# 8_-_Z7010_B34_AR238_MIPI.net
KiCad netlist of a schematic drawn in Altium Designer
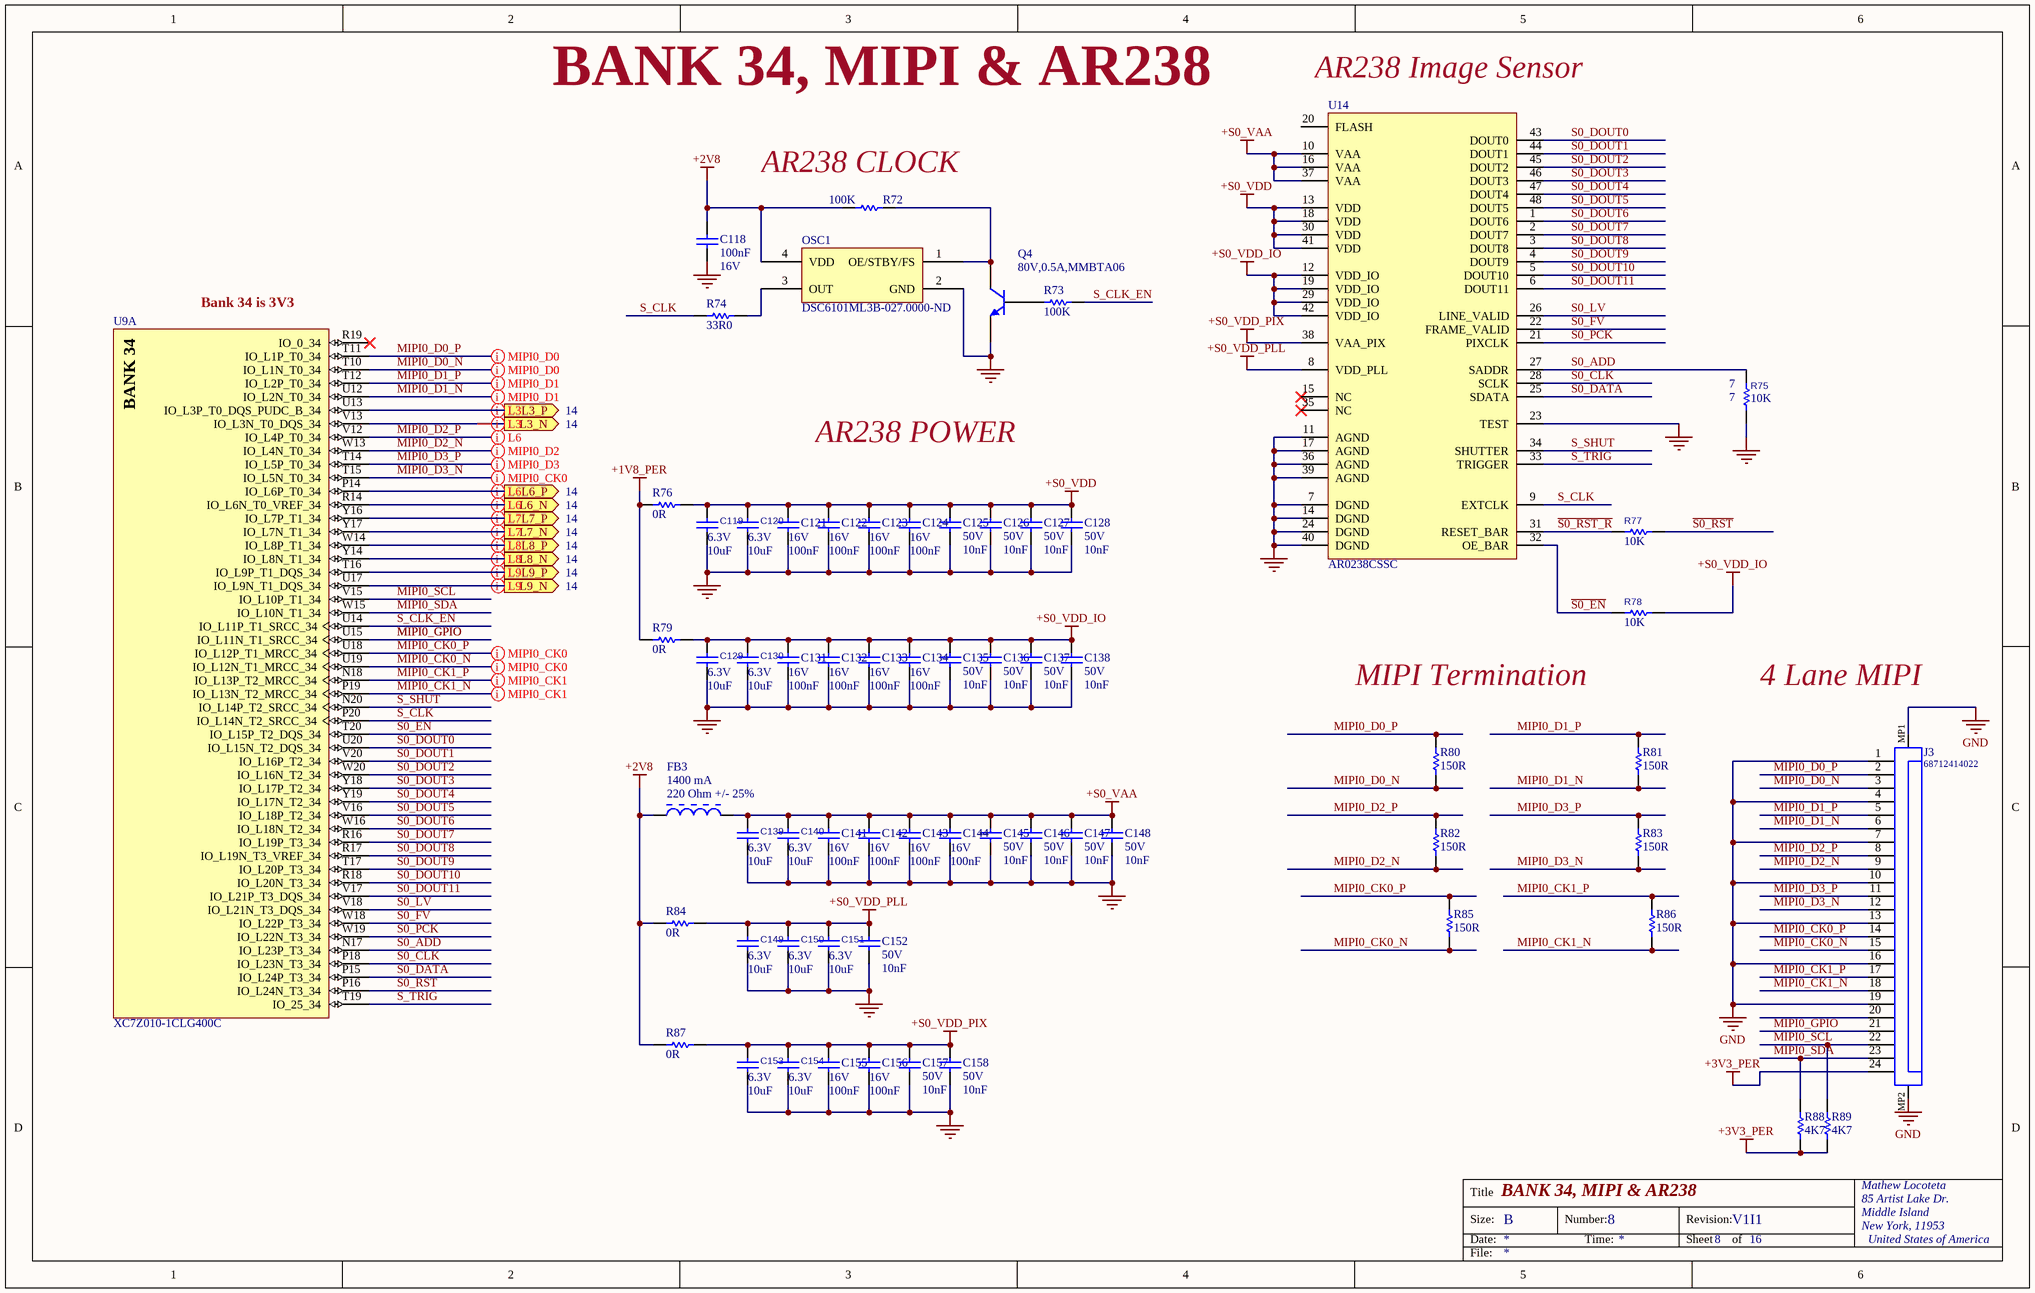
[diagram p0: [8] - Z7010 B34, AR238, MIPI.SchDoc]

(export (version "E")
  (design (tool "Eeschema 10.0.6"))
  (components
    (comp (ref "C118")
      (value "0.1uF,16V")
      (footprint "C0402")
      (description "CAP CER 0.1UF 16V X7R 0402")
      (fields
        (field (name "MANUFACTURER") "Samsung")
        (field (name "MANUFACTURER PART NUMBER") "CL05B104KO5VPNC")
        (field (name "CAPACITANCE") "100nF")
        (field (name "VOLTAGE RATING") "16V")
      )
      (libsource (lib "DVXC4+ ECU (2)") (part "CL05B104KO5VPNC"))
    )
    (comp (ref "C119")
      (value "10uF,6V3")
      (footprint "C0603")
      (description "CAP CER 10UF 6.3V X5R 0603")
      (fields
        (field (name "MANUFACTURER") "Taiyo Yuden")
        (field (name "MANUFACTURER PART NUMBER") "JMK107ABJ106MAHT")
        (field (name "CAPACITANCE") "10uF")
        (field (name "VOLTAGE RATING") "6.3V")
      )
      (libsource (lib "DVXC4+ ECU (2)") (part "JMK107ABJ106MAHT"))
    )
    (comp (ref "C120")
      (value "10uF,6V3")
      (footprint "C0603")
      (description "CAP CER 10UF 6.3V X5R 0603")
      (fields
        (field (name "MANUFACTURER") "Taiyo Yuden")
        (field (name "MANUFACTURER PART NUMBER") "JMK107ABJ106MAHT")
        (field (name "CAPACITANCE") "10uF")
        (field (name "VOLTAGE RATING") "6.3V")
      )
      (libsource (lib "DVXC4+ ECU (2)") (part "JMK107ABJ106MAHT"))
    )
    (comp (ref "C121")
      (value "0.1uF,16V")
      (footprint "C0402")
      (description "CAP CER 0.1UF 16V X7R 0402")
      (fields
        (field (name "MANUFACTURER") "Samsung")
        (field (name "MANUFACTURER PART NUMBER") "CL05B104KO5VPNC")
        (field (name "CAPACITANCE") "100nF")
        (field (name "VOLTAGE RATING") "16V")
      )
      (libsource (lib "DVXC4+ ECU (2)") (part "CL05B104KO5VPNC"))
    )
    (comp (ref "C122")
      (value "0.1uF,16V")
      (footprint "C0402")
      (description "CAP CER 0.1UF 16V X7R 0402")
      (fields
        (field (name "MANUFACTURER") "Samsung")
        (field (name "MANUFACTURER PART NUMBER") "CL05B104KO5VPNC")
        (field (name "CAPACITANCE") "100nF")
        (field (name "VOLTAGE RATING") "16V")
      )
      (libsource (lib "DVXC4+ ECU (2)") (part "CL05B104KO5VPNC"))
    )
    (comp (ref "C123")
      (value "0.1uF,16V")
      (footprint "C0402")
      (description "CAP CER 0.1UF 16V X7R 0402")
      (fields
        (field (name "MANUFACTURER") "Samsung")
        (field (name "MANUFACTURER PART NUMBER") "CL05B104KO5VPNC")
        (field (name "CAPACITANCE") "100nF")
        (field (name "VOLTAGE RATING") "16V")
      )
      (libsource (lib "DVXC4+ ECU (2)") (part "CL05B104KO5VPNC"))
    )
    (comp (ref "C124")
      (value "0.1uF,16V")
      (footprint "C0402")
      (description "CAP CER 0.1UF 16V X7R 0402")
      (fields
        (field (name "MANUFACTURER") "Samsung")
        (field (name "MANUFACTURER PART NUMBER") "CL05B104KO5VPNC")
        (field (name "CAPACITANCE") "100nF")
        (field (name "VOLTAGE RATING") "16V")
      )
      (libsource (lib "DVXC4+ ECU (2)") (part "CL05B104KO5VPNC"))
    )
    (comp (ref "C125")
      (value "CC0402KRX7R9BB103")
      (footprint "CAPC1005X55X25ML5T10")
      (description "Chip Capacitor, 10 nF, +/- 10%, 50 V, -55 to 125 degC, 0402 (1005 Metric), RoHS, Tape and Reel")
      (fields
        (field (name "MANUFACTURER") "Yageo")
        (field (name "VOLTAGE RATING (DC)") "50V")
        (field (name "TOLERANCE") "10%")
        (field (name "CAPACITANCE") "10nF")
      )
      (libsource (lib "Altium Content Vault") (part "CAP-NP-2"))
    )
    (comp (ref "C126")
      (value "CC0402KRX7R9BB103")
      (footprint "CAPC1005X55X25ML5T10")
      (description "Chip Capacitor, 10 nF, +/- 10%, 50 V, -55 to 125 degC, 0402 (1005 Metric), RoHS, Tape and Reel")
      (fields
        (field (name "MANUFACTURER") "Yageo")
        (field (name "VOLTAGE RATING (DC)") "50V")
        (field (name "TOLERANCE") "10%")
        (field (name "CAPACITANCE") "10nF")
      )
      (libsource (lib "Altium Content Vault") (part "CAP-NP-2"))
    )
    (comp (ref "C127")
      (value "CC0402KRX7R9BB103")
      (footprint "CAPC1005X55X25ML5T10")
      (description "Chip Capacitor, 10 nF, +/- 10%, 50 V, -55 to 125 degC, 0402 (1005 Metric), RoHS, Tape and Reel")
      (fields
        (field (name "MANUFACTURER") "Yageo")
        (field (name "VOLTAGE RATING (DC)") "50V")
        (field (name "TOLERANCE") "10%")
        (field (name "CAPACITANCE") "10nF")
      )
      (libsource (lib "Altium Content Vault") (part "CAP-NP-2"))
    )
    (comp (ref "C128")
      (value "CC0402KRX7R9BB103")
      (footprint "CAPC1005X55X25ML5T10")
      (description "Chip Capacitor, 10 nF, +/- 10%, 50 V, -55 to 125 degC, 0402 (1005 Metric), RoHS, Tape and Reel")
      (fields
        (field (name "MANUFACTURER") "Yageo")
        (field (name "VOLTAGE RATING (DC)") "50V")
        (field (name "TOLERANCE") "10%")
        (field (name "CAPACITANCE") "10nF")
      )
      (libsource (lib "Altium Content Vault") (part "CAP-NP-2"))
    )
    (comp (ref "C129")
      (value "10uF,6V3")
      (footprint "C0603")
      (description "CAP CER 10UF 6.3V X5R 0603")
      (fields
        (field (name "MANUFACTURER") "Taiyo Yuden")
        (field (name "MANUFACTURER PART NUMBER") "JMK107ABJ106MAHT")
        (field (name "CAPACITANCE") "10uF")
        (field (name "VOLTAGE RATING") "6.3V")
      )
      (libsource (lib "DVXC4+ ECU (2)") (part "JMK107ABJ106MAHT"))
    )
    (comp (ref "C130")
      (value "10uF,6V3")
      (footprint "C0603")
      (description "CAP CER 10UF 6.3V X5R 0603")
      (fields
        (field (name "MANUFACTURER") "Taiyo Yuden")
        (field (name "MANUFACTURER PART NUMBER") "JMK107ABJ106MAHT")
        (field (name "CAPACITANCE") "10uF")
        (field (name "VOLTAGE RATING") "6.3V")
      )
      (libsource (lib "DVXC4+ ECU (2)") (part "JMK107ABJ106MAHT"))
    )
    (comp (ref "C131")
      (value "0.1uF,16V")
      (footprint "C0402")
      (description "CAP CER 0.1UF 16V X7R 0402")
      (fields
        (field (name "MANUFACTURER") "Samsung")
        (field (name "MANUFACTURER PART NUMBER") "CL05B104KO5VPNC")
        (field (name "CAPACITANCE") "100nF")
        (field (name "VOLTAGE RATING") "16V")
      )
      (libsource (lib "DVXC4+ ECU (2)") (part "CL05B104KO5VPNC"))
    )
    (comp (ref "C132")
      (value "0.1uF,16V")
      (footprint "C0402")
      (description "CAP CER 0.1UF 16V X7R 0402")
      (fields
        (field (name "MANUFACTURER") "Samsung")
        (field (name "MANUFACTURER PART NUMBER") "CL05B104KO5VPNC")
        (field (name "CAPACITANCE") "100nF")
        (field (name "VOLTAGE RATING") "16V")
      )
      (libsource (lib "DVXC4+ ECU (2)") (part "CL05B104KO5VPNC"))
    )
    (comp (ref "C133")
      (value "0.1uF,16V")
      (footprint "C0402")
      (description "CAP CER 0.1UF 16V X7R 0402")
      (fields
        (field (name "MANUFACTURER") "Samsung")
        (field (name "MANUFACTURER PART NUMBER") "CL05B104KO5VPNC")
        (field (name "CAPACITANCE") "100nF")
        (field (name "VOLTAGE RATING") "16V")
      )
      (libsource (lib "DVXC4+ ECU (2)") (part "CL05B104KO5VPNC"))
    )
    (comp (ref "C134")
      (value "0.1uF,16V")
      (footprint "C0402")
      (description "CAP CER 0.1UF 16V X7R 0402")
      (fields
        (field (name "MANUFACTURER") "Samsung")
        (field (name "MANUFACTURER PART NUMBER") "CL05B104KO5VPNC")
        (field (name "CAPACITANCE") "100nF")
        (field (name "VOLTAGE RATING") "16V")
      )
      (libsource (lib "DVXC4+ ECU (2)") (part "CL05B104KO5VPNC"))
    )
    (comp (ref "C135")
      (value "CC0402KRX7R9BB103")
      (footprint "CAPC1005X55X25ML5T10")
      (description "Chip Capacitor, 10 nF, +/- 10%, 50 V, -55 to 125 degC, 0402 (1005 Metric), RoHS, Tape and Reel")
      (fields
        (field (name "MANUFACTURER") "Yageo")
        (field (name "VOLTAGE RATING (DC)") "50V")
        (field (name "TOLERANCE") "10%")
        (field (name "CAPACITANCE") "10nF")
      )
      (libsource (lib "Altium Content Vault") (part "CAP-NP-2"))
    )
    (comp (ref "C136")
      (value "CC0402KRX7R9BB103")
      (footprint "CAPC1005X55X25ML5T10")
      (description "Chip Capacitor, 10 nF, +/- 10%, 50 V, -55 to 125 degC, 0402 (1005 Metric), RoHS, Tape and Reel")
      (fields
        (field (name "MANUFACTURER") "Yageo")
        (field (name "VOLTAGE RATING (DC)") "50V")
        (field (name "TOLERANCE") "10%")
        (field (name "CAPACITANCE") "10nF")
      )
      (libsource (lib "Altium Content Vault") (part "CAP-NP-2"))
    )
    (comp (ref "C137")
      (value "CC0402KRX7R9BB103")
      (footprint "CAPC1005X55X25ML5T10")
      (description "Chip Capacitor, 10 nF, +/- 10%, 50 V, -55 to 125 degC, 0402 (1005 Metric), RoHS, Tape and Reel")
      (fields
        (field (name "MANUFACTURER") "Yageo")
        (field (name "VOLTAGE RATING (DC)") "50V")
        (field (name "TOLERANCE") "10%")
        (field (name "CAPACITANCE") "10nF")
      )
      (libsource (lib "Altium Content Vault") (part "CAP-NP-2"))
    )
    (comp (ref "C138")
      (value "CC0402KRX7R9BB103")
      (footprint "CAPC1005X55X25ML5T10")
      (description "Chip Capacitor, 10 nF, +/- 10%, 50 V, -55 to 125 degC, 0402 (1005 Metric), RoHS, Tape and Reel")
      (fields
        (field (name "MANUFACTURER") "Yageo")
        (field (name "VOLTAGE RATING (DC)") "50V")
        (field (name "TOLERANCE") "10%")
        (field (name "CAPACITANCE") "10nF")
      )
      (libsource (lib "Altium Content Vault") (part "CAP-NP-2"))
    )
    (comp (ref "C139")
      (value "10uF,6V3")
      (footprint "C0603")
      (description "CAP CER 10UF 6.3V X5R 0603")
      (fields
        (field (name "MANUFACTURER") "Taiyo Yuden")
        (field (name "MANUFACTURER PART NUMBER") "JMK107ABJ106MAHT")
        (field (name "CAPACITANCE") "10uF")
        (field (name "VOLTAGE RATING") "6.3V")
      )
      (libsource (lib "DVXC4+ ECU (2)") (part "JMK107ABJ106MAHT"))
    )
    (comp (ref "C140")
      (value "10uF,6V3")
      (footprint "C0603")
      (description "CAP CER 10UF 6.3V X5R 0603")
      (fields
        (field (name "MANUFACTURER") "Taiyo Yuden")
        (field (name "MANUFACTURER PART NUMBER") "JMK107ABJ106MAHT")
        (field (name "CAPACITANCE") "10uF")
        (field (name "VOLTAGE RATING") "6.3V")
      )
      (libsource (lib "DVXC4+ ECU (2)") (part "JMK107ABJ106MAHT"))
    )
    (comp (ref "C141")
      (value "0.1uF,16V")
      (footprint "C0402")
      (description "CAP CER 0.1UF 16V X7R 0402")
      (fields
        (field (name "MANUFACTURER") "Samsung")
        (field (name "MANUFACTURER PART NUMBER") "CL05B104KO5VPNC")
        (field (name "CAPACITANCE") "100nF")
        (field (name "VOLTAGE RATING") "16V")
      )
      (libsource (lib "DVXC4+ ECU (2)") (part "CL05B104KO5VPNC"))
    )
    (comp (ref "C142")
      (value "0.1uF,16V")
      (footprint "C0402")
      (description "CAP CER 0.1UF 16V X7R 0402")
      (fields
        (field (name "MANUFACTURER") "Samsung")
        (field (name "MANUFACTURER PART NUMBER") "CL05B104KO5VPNC")
        (field (name "CAPACITANCE") "100nF")
        (field (name "VOLTAGE RATING") "16V")
      )
      (libsource (lib "DVXC4+ ECU (2)") (part "CL05B104KO5VPNC"))
    )
    (comp (ref "C143")
      (value "0.1uF,16V")
      (footprint "C0402")
      (description "CAP CER 0.1UF 16V X7R 0402")
      (fields
        (field (name "MANUFACTURER") "Samsung")
        (field (name "MANUFACTURER PART NUMBER") "CL05B104KO5VPNC")
        (field (name "CAPACITANCE") "100nF")
        (field (name "VOLTAGE RATING") "16V")
      )
      (libsource (lib "DVXC4+ ECU (2)") (part "CL05B104KO5VPNC"))
    )
    (comp (ref "C144")
      (value "0.1uF,16V")
      (footprint "C0402")
      (description "CAP CER 0.1UF 16V X7R 0402")
      (fields
        (field (name "MANUFACTURER") "Samsung")
        (field (name "MANUFACTURER PART NUMBER") "CL05B104KO5VPNC")
        (field (name "CAPACITANCE") "100nF")
        (field (name "VOLTAGE RATING") "16V")
      )
      (libsource (lib "DVXC4+ ECU (2)") (part "CL05B104KO5VPNC"))
    )
    (comp (ref "C145")
      (value "CC0402KRX7R9BB103")
      (footprint "CAPC1005X55X25ML5T10")
      (description "Chip Capacitor, 10 nF, +/- 10%, 50 V, -55 to 125 degC, 0402 (1005 Metric), RoHS, Tape and Reel")
      (fields
        (field (name "MANUFACTURER") "Yageo")
        (field (name "VOLTAGE RATING (DC)") "50V")
        (field (name "TOLERANCE") "10%")
        (field (name "CAPACITANCE") "10nF")
      )
      (libsource (lib "Altium Content Vault") (part "CAP-NP-2"))
    )
    (comp (ref "C146")
      (value "CC0402KRX7R9BB103")
      (footprint "CAPC1005X55X25ML5T10")
      (description "Chip Capacitor, 10 nF, +/- 10%, 50 V, -55 to 125 degC, 0402 (1005 Metric), RoHS, Tape and Reel")
      (fields
        (field (name "MANUFACTURER") "Yageo")
        (field (name "VOLTAGE RATING (DC)") "50V")
        (field (name "TOLERANCE") "10%")
        (field (name "CAPACITANCE") "10nF")
      )
      (libsource (lib "Altium Content Vault") (part "CAP-NP-2"))
    )
    (comp (ref "C147")
      (value "CC0402KRX7R9BB103")
      (footprint "CAPC1005X55X25ML5T10")
      (description "Chip Capacitor, 10 nF, +/- 10%, 50 V, -55 to 125 degC, 0402 (1005 Metric), RoHS, Tape and Reel")
      (fields
        (field (name "MANUFACTURER") "Yageo")
        (field (name "VOLTAGE RATING (DC)") "50V")
        (field (name "TOLERANCE") "10%")
        (field (name "CAPACITANCE") "10nF")
      )
      (libsource (lib "Altium Content Vault") (part "CAP-NP-2"))
    )
    (comp (ref "C148")
      (value "CC0402KRX7R9BB103")
      (footprint "CAPC1005X55X25ML5T10")
      (description "Chip Capacitor, 10 nF, +/- 10%, 50 V, -55 to 125 degC, 0402 (1005 Metric), RoHS, Tape and Reel")
      (fields
        (field (name "MANUFACTURER") "Yageo")
        (field (name "VOLTAGE RATING (DC)") "50V")
        (field (name "TOLERANCE") "10%")
        (field (name "CAPACITANCE") "10nF")
      )
      (libsource (lib "Altium Content Vault") (part "CAP-NP-2"))
    )
    (comp (ref "C149")
      (value "10uF,6V3")
      (footprint "C0603")
      (description "CAP CER 10UF 6.3V X5R 0603")
      (fields
        (field (name "MANUFACTURER") "Taiyo Yuden")
        (field (name "MANUFACTURER PART NUMBER") "JMK107ABJ106MAHT")
        (field (name "CAPACITANCE") "10uF")
        (field (name "VOLTAGE RATING") "6.3V")
      )
      (libsource (lib "DVXC4+ ECU (2)") (part "JMK107ABJ106MAHT"))
    )
    (comp (ref "C150")
      (value "10uF,6V3")
      (footprint "C0603")
      (description "CAP CER 10UF 6.3V X5R 0603")
      (fields
        (field (name "MANUFACTURER") "Taiyo Yuden")
        (field (name "MANUFACTURER PART NUMBER") "JMK107ABJ106MAHT")
        (field (name "CAPACITANCE") "10uF")
        (field (name "VOLTAGE RATING") "6.3V")
      )
      (libsource (lib "DVXC4+ ECU (2)") (part "JMK107ABJ106MAHT"))
    )
    (comp (ref "C151")
      (value "10uF,6V3")
      (footprint "C0603")
      (description "CAP CER 10UF 6.3V X5R 0603")
      (fields
        (field (name "MANUFACTURER") "Taiyo Yuden")
        (field (name "MANUFACTURER PART NUMBER") "JMK107ABJ106MAHT")
        (field (name "CAPACITANCE") "10uF")
        (field (name "VOLTAGE RATING") "6.3V")
      )
      (libsource (lib "DVXC4+ ECU (2)") (part "JMK107ABJ106MAHT"))
    )
    (comp (ref "C152")
      (value "CC0402KRX7R9BB103")
      (footprint "CAPC1005X55X25ML5T10")
      (description "Chip Capacitor, 10 nF, +/- 10%, 50 V, -55 to 125 degC, 0402 (1005 Metric), RoHS, Tape and Reel")
      (fields
        (field (name "MANUFACTURER") "Yageo")
        (field (name "VOLTAGE RATING (DC)") "50V")
        (field (name "TOLERANCE") "10%")
        (field (name "CAPACITANCE") "10nF")
      )
      (libsource (lib "Altium Content Vault") (part "CAP-NP-2"))
    )
    (comp (ref "C153")
      (value "10uF,6V3")
      (footprint "C0603")
      (description "CAP CER 10UF 6.3V X5R 0603")
      (fields
        (field (name "MANUFACTURER") "Taiyo Yuden")
        (field (name "MANUFACTURER PART NUMBER") "JMK107ABJ106MAHT")
        (field (name "CAPACITANCE") "10uF")
        (field (name "VOLTAGE RATING") "6.3V")
      )
      (libsource (lib "DVXC4+ ECU (2)") (part "JMK107ABJ106MAHT"))
    )
    (comp (ref "C154")
      (value "10uF,6V3")
      (footprint "C0603")
      (description "CAP CER 10UF 6.3V X5R 0603")
      (fields
        (field (name "MANUFACTURER") "Taiyo Yuden")
        (field (name "MANUFACTURER PART NUMBER") "JMK107ABJ106MAHT")
        (field (name "CAPACITANCE") "10uF")
        (field (name "VOLTAGE RATING") "6.3V")
      )
      (libsource (lib "DVXC4+ ECU (2)") (part "JMK107ABJ106MAHT"))
    )
    (comp (ref "C155")
      (value "0.1uF,16V")
      (footprint "C0402")
      (description "CAP CER 0.1UF 16V X7R 0402")
      (fields
        (field (name "MANUFACTURER") "Samsung")
        (field (name "MANUFACTURER PART NUMBER") "CL05B104KO5VPNC")
        (field (name "CAPACITANCE") "100nF")
        (field (name "VOLTAGE RATING") "16V")
      )
      (libsource (lib "DVXC4+ ECU (2)") (part "CL05B104KO5VPNC"))
    )
    (comp (ref "C156")
      (value "0.1uF,16V")
      (footprint "C0402")
      (description "CAP CER 0.1UF 16V X7R 0402")
      (fields
        (field (name "MANUFACTURER") "Samsung")
        (field (name "MANUFACTURER PART NUMBER") "CL05B104KO5VPNC")
        (field (name "CAPACITANCE") "100nF")
        (field (name "VOLTAGE RATING") "16V")
      )
      (libsource (lib "DVXC4+ ECU (2)") (part "CL05B104KO5VPNC"))
    )
    (comp (ref "C157")
      (value "CC0402KRX7R9BB103")
      (footprint "CAPC1005X55X25ML5T10")
      (description "Chip Capacitor, 10 nF, +/- 10%, 50 V, -55 to 125 degC, 0402 (1005 Metric), RoHS, Tape and Reel")
      (fields
        (field (name "MANUFACTURER") "Yageo")
        (field (name "VOLTAGE RATING (DC)") "50V")
        (field (name "TOLERANCE") "10%")
        (field (name "CAPACITANCE") "10nF")
      )
      (libsource (lib "Altium Content Vault") (part "CAP-NP-2"))
    )
    (comp (ref "C158")
      (value "CC0402KRX7R9BB103")
      (footprint "CAPC1005X55X25ML5T10")
      (description "Chip Capacitor, 10 nF, +/- 10%, 50 V, -55 to 125 degC, 0402 (1005 Metric), RoHS, Tape and Reel")
      (fields
        (field (name "MANUFACTURER") "Yageo")
        (field (name "VOLTAGE RATING (DC)") "50V")
        (field (name "TOLERANCE") "10%")
        (field (name "CAPACITANCE") "10nF")
      )
      (libsource (lib "Altium Content Vault") (part "CAP-NP-2"))
    )
    (comp (ref "FB3")
      (value "BLM18PG221SN1D")
      (footprint "MURA-BLM18PG_KG-CHIP-2_V2")
      (fields
        (field (name "RATED CURRENT") "1400 mA")
        (field (name "IMPEDANCE (AT 100 MHZ)") "220 Ohm +/- 25%")
        (field (name "MANUFACTURER") "Murata")
      )
      (libsource (lib "Altium Content Vault") (part "MURA-FB-2"))
    )
    (comp (ref "J3")
      (value "68712414022")
      (footprint "68712414022")
      (description "SMT ZIF Connectors WR-FPC, Horizontal, Top Contact, pitch 0.5 mm, 24 pins")
      (fields (field (name "MANUFACTURER") "Wurth Elektronik") (field (name "PUBLISHER") "WurthElektronik"))
      (libsource (lib "Altium Content Vault") (part "WE-6871241XXX22-24"))
    )
    (comp (ref "OSC1")
      (value "DSC6101ML3B-027.0000-ND")
      (footprint "4-VFLGA")
      (description "ULTRA-LOW POWER,MEMS OSCILLATOR,\r\nDSC6101ML3B-027.0000-ND\r\nUSE B VERSION 4-VFLGA 2MMx1.6MM")
      (fields
        (field (name "MANUFACTURER") "Microchip")
        (field (name "MANUFACTURER PART NUMBER") "DSC6101CI2A-027.0000")
      )
      (libsource (lib "DVXC4+ ECU (2)") (part "DSC6101CI2A-027.0000"))
    )
    (comp (ref "Q4")
      (value "80V,0.5A,MMBTA06")
      (footprint "ONSC-SOT-23-3-318-08_V")
      (description "TRANS NPN 80V 0.5A SOT23")
      (fields
        (field (name "MANUFACTURER") "ON Semiconductor")
        (field (name "MANUFACTURER PART NUMBER") "MMBTA06LT1G")
      )
      (libsource (lib "DVXC4+ ECU (2)") (part "MMBTA06LT1G"))
    )
    (comp (ref "R72")
      (value "100K")
      (footprint "R0402")
      (description "RES 100K OHM 1% 1/16W 0402")
      (fields
        (field (name "MANUFACTURER") "Stackpole Electronics")
        (field (name "MANUFACTURER PART NUMBER") "RMCF0402FT100K")
      )
      (libsource (lib "DVXC4+ ECU (2)") (part "RMCF0402FT100K"))
    )
    (comp (ref "R73")
      (value "100K")
      (footprint "R0402")
      (description "RES 100K OHM 1% 1/16W 0402")
      (fields
        (field (name "MANUFACTURER") "Stackpole Electronics")
        (field (name "MANUFACTURER PART NUMBER") "RMCF0402FT100K")
      )
      (libsource (lib "DVXC4+ ECU (2)") (part "RMCF0402FT100K"))
    )
    (comp (ref "R74")
      (value "33R0")
      (footprint "R0603")
      (description "RES 33 OHM 1% 1/10W 0603")
      (fields
        (field (name "MANUFACTURER") "Stackpole Electronics")
        (field (name "MANUFACTURER PART NUMBER") "RMCF0603FT33R0")
      )
      (libsource (lib "DVXC4+ ECU (2)") (part "RMCF0603FT33R0"))
    )
    (comp (ref "R75")
      (value "10K")
      (footprint "R0402")
      (description "RES 10K OHM 1% 1/16W 0402")
      (fields
        (field (name "MANUFACTURER") "Stackpole Electronics")
        (field (name "MANUFACTURER PART NUMBER") "RMCF0402FT10K0")
      )
      (libsource (lib "DVXC4+ ECU (2)") (part "RMCF0402FT10K0"))
    )
    (comp (ref "R76")
      (value "0R")
      (footprint "R0402")
      (description "RES 0 OHM JUMPER 1/16W 0402")
      (fields
        (field (name "MANUFACTURER") "Stackpole Electronics")
        (field (name "MANUFACTURER PART NUMBER") "RMCF0402ZT0R00")
      )
      (libsource (lib "DVXC4+ ECU (2)") (part "RMCF0402ZT0R00"))
    )
    (comp (ref "R77")
      (value "10K")
      (footprint "R0402")
      (description "RES 10K OHM 1% 1/16W 0402")
      (fields
        (field (name "MANUFACTURER") "Stackpole Electronics")
        (field (name "MANUFACTURER PART NUMBER") "RMCF0402FT10K0")
      )
      (libsource (lib "DVXC4+ ECU (2)") (part "RMCF0402FT10K0"))
    )
    (comp (ref "R78")
      (value "10K")
      (footprint "R0402")
      (description "RES 10K OHM 1% 1/16W 0402")
      (fields
        (field (name "MANUFACTURER") "Stackpole Electronics")
        (field (name "MANUFACTURER PART NUMBER") "RMCF0402FT10K0")
      )
      (libsource (lib "DVXC4+ ECU (2)") (part "RMCF0402FT10K0"))
    )
    (comp (ref "R79")
      (value "0R")
      (footprint "R0402")
      (description "RES 0 OHM JUMPER 1/16W 0402")
      (fields
        (field (name "MANUFACTURER") "Stackpole Electronics")
        (field (name "MANUFACTURER PART NUMBER") "RMCF0402ZT0R00")
      )
      (libsource (lib "DVXC4+ ECU (2)") (part "RMCF0402ZT0R00"))
    )
    (comp (ref "R80")
      (value "150R")
      (footprint "RESC1005X40X25LL05T05")
      (fields (field (name "PART NUMBER") "CRCW0402150RFKED") (field (name "MANUFACTURER") "Vishay Dale"))
      (libsource (lib "Altium Content Vault") (part "RES"))
    )
    (comp (ref "R81")
      (value "150R")
      (footprint "RESC1005X40X25LL05T05")
      (fields (field (name "PART NUMBER") "CRCW0402150RFKED") (field (name "MANUFACTURER") "Vishay Dale"))
      (libsource (lib "Altium Content Vault") (part "RES"))
    )
    (comp (ref "R82")
      (value "150R")
      (footprint "RESC1005X40X25LL05T05")
      (fields (field (name "PART NUMBER") "CRCW0402150RFKED") (field (name "MANUFACTURER") "Vishay Dale"))
      (libsource (lib "Altium Content Vault") (part "RES"))
    )
    (comp (ref "R83")
      (value "150R")
      (footprint "RESC1005X40X25LL05T05")
      (fields (field (name "PART NUMBER") "CRCW0402150RFKED") (field (name "MANUFACTURER") "Vishay Dale"))
      (libsource (lib "Altium Content Vault") (part "RES"))
    )
    (comp (ref "R84")
      (value "0R")
      (footprint "R0402")
      (description "RES 0 OHM JUMPER 1/16W 0402")
      (fields
        (field (name "MANUFACTURER") "Stackpole Electronics")
        (field (name "MANUFACTURER PART NUMBER") "RMCF0402ZT0R00")
      )
      (libsource (lib "DVXC4+ ECU (2)") (part "RMCF0402ZT0R00"))
    )
    (comp (ref "R85")
      (value "150R")
      (footprint "RESC1005X40X25LL05T05")
      (fields (field (name "PART NUMBER") "CRCW0402150RFKED") (field (name "MANUFACTURER") "Vishay Dale"))
      (libsource (lib "Altium Content Vault") (part "RES"))
    )
    (comp (ref "R86")
      (value "150R")
      (footprint "RESC1005X40X25LL05T05")
      (fields (field (name "PART NUMBER") "CRCW0402150RFKED") (field (name "MANUFACTURER") "Vishay Dale"))
      (libsource (lib "Altium Content Vault") (part "RES"))
    )
    (comp (ref "R87")
      (value "0R")
      (footprint "R0402")
      (description "RES 0 OHM JUMPER 1/16W 0402")
      (fields
        (field (name "MANUFACTURER") "Stackpole Electronics")
        (field (name "MANUFACTURER PART NUMBER") "RMCF0402ZT0R00")
      )
      (libsource (lib "DVXC4+ ECU (2)") (part "RMCF0402ZT0R00"))
    )
    (comp (ref "R88")
      (value "4K7 0402 1%")
      (description "Resistor SMD 4.7 kOhm 0402 PU=10000 ST, CRCW04024K70FKED, Vishay")
      (fields
        (field (name "MANUFACTURER") "Vishay")
        (field (name "MANUFACTURER PART NUMBER") "CRCW04024K70FKED")
        (field (name "RESISTANCE") "4K7")
      )
      (libsource (lib "Zynq 7000") (part "CRCW04024K70FKED"))
    )
    (comp (ref "R89")
      (value "4K7 0402 1%")
      (description "Resistor SMD 4.7 kOhm 0402 PU=10000 ST, CRCW04024K70FKED, Vishay")
      (fields
        (field (name "MANUFACTURER") "Vishay")
        (field (name "MANUFACTURER PART NUMBER") "CRCW04024K70FKED")
        (field (name "RESISTANCE") "4K7")
      )
      (libsource (lib "Zynq 7000") (part "CRCW04024K70FKED"))
    )
    (comp (ref "U9")
      (value "XC7Z010-1CLG400C")
      (footprint "CLG400")
      (fields (field (name "GENERIC PART NUMBER") "XC7Z010"))
      (libsource (lib "Altium Content Vault") (part "XNLX-XC7Z010-CLG400"))
    )
    (comp (ref "U14")
      (value "AR0238CSSC")
      (fields
        (field (name "MANUFACTURER") "ON Semiconductor")
        (field (name "MANUFACTURER PART NUMBER") "AR0238CSSC12SPRA0-DR1")
      )
      (libsource (lib "DVXC4+ ECU (2)") (part "AR0238CSSC12SPRA0-DR1"))
    )
  )
  (nets
    (net (code "1") (name "+1V8_PER") (class "Default")
      (node (ref "R76") (pin "1") (pinfunction "1_1") (pintype "passive"))
      (node (ref "R79") (pin "1") (pinfunction "1_1") (pintype "passive"))
    )
    (net (code "2") (name "+2V8") (class "Default")
      (node (ref "C118") (pin "1") (pinfunction "1_1") (pintype "passive"))
      (node (ref "FB3") (pin "1") (pinfunction "1_1") (pintype "passive"))
      (node (ref "OSC1") (pin "4") (pinfunction "VDD_4") (pintype "power_in"))
      (node (ref "R72") (pin "1") (pinfunction "1_1") (pintype "passive"))
      (node (ref "R84") (pin "1") (pinfunction "1_1") (pintype "passive"))
      (node (ref "R87") (pin "1") (pinfunction "1_1") (pintype "passive"))
    )
    (net (code "3") (name "+3V3_PER") (class "Default")
      (node (ref "J3") (pin "24") (pinfunction "24_24") (pintype "passive"))
      (node (ref "R88") (pin "2") (pinfunction "2_2") (pintype "passive"))
      (node (ref "R89") (pin "2") (pinfunction "2_2") (pintype "passive"))
    )
    (net (code "4") (name "+S0_VAA") (class "Default")
      (node (ref "C139") (pin "2") (pinfunction "2_2") (pintype "passive"))
      (node (ref "C140") (pin "2") (pinfunction "2_2") (pintype "passive"))
      (node (ref "C141") (pin "2") (pinfunction "2_2") (pintype "passive"))
      (node (ref "C142") (pin "2") (pinfunction "2_2") (pintype "passive"))
      (node (ref "C143") (pin "2") (pinfunction "2_2") (pintype "passive"))
      (node (ref "C144") (pin "2") (pinfunction "2_2") (pintype "passive"))
      (node (ref "C145") (pin "2") (pinfunction "2_2") (pintype "passive"))
      (node (ref "C146") (pin "2") (pinfunction "2_2") (pintype "passive"))
      (node (ref "C147") (pin "2") (pinfunction "2_2") (pintype "passive"))
      (node (ref "C148") (pin "2") (pinfunction "2_2") (pintype "passive"))
      (node (ref "FB3") (pin "2") (pinfunction "2_2") (pintype "passive"))
      (node (ref "U14") (pin "10") (pinfunction "VAA_10") (pintype "passive"))
      (node (ref "U14") (pin "16") (pinfunction "VAA_16") (pintype "passive"))
      (node (ref "U14") (pin "37") (pinfunction "VAA_37") (pintype "passive"))
    )
    (net (code "5") (name "+S0_VDD") (class "Default")
      (node (ref "C119") (pin "2") (pinfunction "2_2") (pintype "passive"))
      (node (ref "C120") (pin "2") (pinfunction "2_2") (pintype "passive"))
      (node (ref "C121") (pin "2") (pinfunction "2_2") (pintype "passive"))
      (node (ref "C122") (pin "2") (pinfunction "2_2") (pintype "passive"))
      (node (ref "C123") (pin "2") (pinfunction "2_2") (pintype "passive"))
      (node (ref "C124") (pin "2") (pinfunction "2_2") (pintype "passive"))
      (node (ref "C125") (pin "2") (pinfunction "2_2") (pintype "passive"))
      (node (ref "C126") (pin "2") (pinfunction "2_2") (pintype "passive"))
      (node (ref "C127") (pin "2") (pinfunction "2_2") (pintype "passive"))
      (node (ref "C128") (pin "2") (pinfunction "2_2") (pintype "passive"))
      (node (ref "R76") (pin "2") (pinfunction "2_2") (pintype "passive"))
      (node (ref "U14") (pin "13") (pinfunction "VDD_13") (pintype "passive"))
      (node (ref "U14") (pin "18") (pinfunction "VDD_18") (pintype "passive"))
      (node (ref "U14") (pin "30") (pinfunction "VDD_30") (pintype "passive"))
      (node (ref "U14") (pin "41") (pinfunction "VDD_41") (pintype "passive"))
    )
    (net (code "6") (name "+S0_VDD_IO") (class "Default")
      (node (ref "C129") (pin "2") (pinfunction "2_2") (pintype "passive"))
      (node (ref "C130") (pin "2") (pinfunction "2_2") (pintype "passive"))
      (node (ref "C131") (pin "2") (pinfunction "2_2") (pintype "passive"))
      (node (ref "C132") (pin "2") (pinfunction "2_2") (pintype "passive"))
      (node (ref "C133") (pin "2") (pinfunction "2_2") (pintype "passive"))
      (node (ref "C134") (pin "2") (pinfunction "2_2") (pintype "passive"))
      (node (ref "C135") (pin "2") (pinfunction "2_2") (pintype "passive"))
      (node (ref "C136") (pin "2") (pinfunction "2_2") (pintype "passive"))
      (node (ref "C137") (pin "2") (pinfunction "2_2") (pintype "passive"))
      (node (ref "C138") (pin "2") (pinfunction "2_2") (pintype "passive"))
      (node (ref "R78") (pin "2") (pinfunction "2_2") (pintype "passive"))
      (node (ref "R79") (pin "2") (pinfunction "2_2") (pintype "passive"))
      (node (ref "U14") (pin "12") (pinfunction "VDD_IO_12") (pintype "passive"))
      (node (ref "U14") (pin "19") (pinfunction "VDD_IO_19") (pintype "passive"))
      (node (ref "U14") (pin "29") (pinfunction "VDD_IO_29") (pintype "passive"))
      (node (ref "U14") (pin "42") (pinfunction "VDD_IO_42") (pintype "passive"))
    )
    (net (code "7") (name "+S0_VDD_PIX") (class "Default")
      (node (ref "C153") (pin "2") (pinfunction "2_2") (pintype "passive"))
      (node (ref "C154") (pin "2") (pinfunction "2_2") (pintype "passive"))
      (node (ref "C155") (pin "2") (pinfunction "2_2") (pintype "passive"))
      (node (ref "C156") (pin "2") (pinfunction "2_2") (pintype "passive"))
      (node (ref "C157") (pin "2") (pinfunction "2_2") (pintype "passive"))
      (node (ref "C158") (pin "2") (pinfunction "2_2") (pintype "passive"))
      (node (ref "R87") (pin "2") (pinfunction "2_2") (pintype "passive"))
      (node (ref "U14") (pin "38") (pinfunction "VAA_PIX_38") (pintype "passive"))
    )
    (net (code "8") (name "+S0_VDD_PLL") (class "Default")
      (node (ref "C149") (pin "2") (pinfunction "2_2") (pintype "passive"))
      (node (ref "C150") (pin "2") (pinfunction "2_2") (pintype "passive"))
      (node (ref "C151") (pin "2") (pinfunction "2_2") (pintype "passive"))
      (node (ref "C152") (pin "2") (pinfunction "2_2") (pintype "passive"))
      (node (ref "R84") (pin "2") (pinfunction "2_2") (pintype "passive"))
      (node (ref "U14") (pin "8") (pinfunction "VDD_PLL_8") (pintype "passive"))
    )
    (net (code "9") (name "/L3_N") (class "Default")
      (node (ref "U9") (pin "V13") (pinfunction "IO_L3N_T0_DQS_34_V13") (pintype "bidirectional"))
    )
    (net (code "10") (name "/L3_P") (class "Default")
      (node (ref "U9") (pin "U13") (pinfunction "IO_L3P_T0_DQS_PUDC_B_34_U13") (pintype "bidirectional"))
    )
    (net (code "11") (name "/L6_N") (class "Default")
      (node (ref "U9") (pin "R14") (pinfunction "IO_L6N_T0_VREF_34_R14") (pintype "bidirectional"))
    )
    (net (code "12") (name "/L6_P") (class "Default")
      (node (ref "U9") (pin "P14") (pinfunction "IO_L6P_T0_34_P14") (pintype "bidirectional"))
    )
    (net (code "13") (name "/L7_N") (class "Default")
      (node (ref "U9") (pin "Y17") (pinfunction "IO_L7N_T1_34_Y17") (pintype "bidirectional"))
    )
    (net (code "14") (name "/L7_P") (class "Default")
      (node (ref "U9") (pin "Y16") (pinfunction "IO_L7P_T1_34_Y16") (pintype "bidirectional"))
    )
    (net (code "15") (name "/L8_N") (class "Default")
      (node (ref "U9") (pin "Y14") (pinfunction "IO_L8N_T1_34_Y14") (pintype "bidirectional"))
    )
    (net (code "16") (name "/L8_P") (class "Default")
      (node (ref "U9") (pin "W14") (pinfunction "IO_L8P_T1_34_W14") (pintype "bidirectional"))
    )
    (net (code "17") (name "/L9_N") (class "Default")
      (node (ref "U9") (pin "U17") (pinfunction "IO_L9N_T1_DQS_34_U17") (pintype "bidirectional"))
    )
    (net (code "18") (name "/L9_P") (class "Default")
      (node (ref "U9") (pin "T16") (pinfunction "IO_L9P_T1_DQS_34_T16") (pintype "bidirectional"))
    )
    (net (code "19") (name "/MIPI0_CK0_N") (class "Default")
      (node (ref "J3") (pin "15") (pinfunction "15_15") (pintype "passive"))
      (node (ref "R85") (pin "1") (pinfunction "1_1") (pintype "passive"))
      (node (ref "U9") (pin "U19") (pinfunction "IO_L12N_T1_MRCC_34_U19") (pintype "bidirectional"))
    )
    (net (code "20") (name "/MIPI0_CK0_P") (class "Default")
      (node (ref "J3") (pin "14") (pinfunction "14_14") (pintype "passive"))
      (node (ref "R85") (pin "2") (pinfunction "2_2") (pintype "passive"))
      (node (ref "U9") (pin "U18") (pinfunction "IO_L12P_T1_MRCC_34_U18") (pintype "bidirectional"))
    )
    (net (code "21") (name "/MIPI0_CK1_N") (class "Default")
      (node (ref "J3") (pin "18") (pinfunction "18_18") (pintype "passive"))
      (node (ref "R86") (pin "1") (pinfunction "1_1") (pintype "passive"))
      (node (ref "U9") (pin "P19") (pinfunction "IO_L13N_T2_MRCC_34_P19") (pintype "bidirectional"))
    )
    (net (code "22") (name "/MIPI0_CK1_P") (class "Default")
      (node (ref "J3") (pin "17") (pinfunction "17_17") (pintype "passive"))
      (node (ref "R86") (pin "2") (pinfunction "2_2") (pintype "passive"))
      (node (ref "U9") (pin "N18") (pinfunction "IO_L13P_T2_MRCC_34_N18") (pintype "bidirectional"))
    )
    (net (code "23") (name "/MIPI0_D0_N") (class "Default")
      (node (ref "J3") (pin "3") (pinfunction "3_3") (pintype "passive"))
      (node (ref "R80") (pin "1") (pinfunction "1_1") (pintype "passive"))
      (node (ref "U9") (pin "T10") (pinfunction "IO_L1N_T0_34_T10") (pintype "bidirectional"))
    )
    (net (code "24") (name "/MIPI0_D0_P") (class "Default")
      (node (ref "J3") (pin "2") (pinfunction "2_2") (pintype "passive"))
      (node (ref "R80") (pin "2") (pinfunction "2_2") (pintype "passive"))
      (node (ref "U9") (pin "T11") (pinfunction "IO_L1P_T0_34_T11") (pintype "bidirectional"))
    )
    (net (code "25") (name "/MIPI0_D1_N") (class "Default")
      (node (ref "J3") (pin "6") (pinfunction "6_6") (pintype "passive"))
      (node (ref "R81") (pin "1") (pinfunction "1_1") (pintype "passive"))
      (node (ref "U9") (pin "U12") (pinfunction "IO_L2N_T0_34_U12") (pintype "bidirectional"))
    )
    (net (code "26") (name "/MIPI0_D1_P") (class "Default")
      (node (ref "J3") (pin "5") (pinfunction "5_5") (pintype "passive"))
      (node (ref "R81") (pin "2") (pinfunction "2_2") (pintype "passive"))
      (node (ref "U9") (pin "T12") (pinfunction "IO_L2P_T0_34_T12") (pintype "bidirectional"))
    )
    (net (code "27") (name "/MIPI0_D2_N") (class "Default")
      (node (ref "J3") (pin "9") (pinfunction "9_9") (pintype "passive"))
      (node (ref "R82") (pin "1") (pinfunction "1_1") (pintype "passive"))
      (node (ref "U9") (pin "W13") (pinfunction "IO_L4N_T0_34_W13") (pintype "bidirectional"))
    )
    (net (code "28") (name "/MIPI0_D2_P") (class "Default")
      (node (ref "J3") (pin "8") (pinfunction "8_8") (pintype "passive"))
      (node (ref "R82") (pin "2") (pinfunction "2_2") (pintype "passive"))
      (node (ref "U9") (pin "V12") (pinfunction "IO_L4P_T0_34_V12") (pintype "bidirectional"))
    )
    (net (code "29") (name "/MIPI0_D3_N") (class "Default")
      (node (ref "J3") (pin "12") (pinfunction "12_12") (pintype "passive"))
      (node (ref "R83") (pin "1") (pinfunction "1_1") (pintype "passive"))
      (node (ref "U9") (pin "T15") (pinfunction "IO_L5N_T0_34_T15") (pintype "bidirectional"))
    )
    (net (code "30") (name "/MIPI0_D3_P") (class "Default")
      (node (ref "J3") (pin "11") (pinfunction "11_11") (pintype "passive"))
      (node (ref "R83") (pin "2") (pinfunction "2_2") (pintype "passive"))
      (node (ref "U9") (pin "T14") (pinfunction "IO_L5P_T0_34_T14") (pintype "bidirectional"))
    )
    (net (code "31") (name "/MIPI0_GPIO") (class "Default")
      (node (ref "J3") (pin "21") (pinfunction "21_21") (pintype "passive"))
      (node (ref "U9") (pin "U15") (pinfunction "IO_L11N_T1_SRCC_34_U15") (pintype "bidirectional"))
    )
    (net (code "32") (name "/MIPI0_SCL") (class "Default")
      (node (ref "J3") (pin "22") (pinfunction "22_22") (pintype "passive"))
      (node (ref "R89") (pin "1") (pinfunction "1_1") (pintype "passive"))
      (node (ref "U9") (pin "V15") (pinfunction "IO_L10P_T1_34_V15") (pintype "bidirectional"))
    )
    (net (code "33") (name "/MIPI0_SDA") (class "Default")
      (node (ref "J3") (pin "23") (pinfunction "23_23") (pintype "passive"))
      (node (ref "R88") (pin "1") (pinfunction "1_1") (pintype "passive"))
      (node (ref "U9") (pin "W15") (pinfunction "IO_L10N_T1_34_W15") (pintype "bidirectional"))
    )
    (net (code "34") (name "/S0_ADD") (class "Default")
      (node (ref "R75") (pin "2") (pinfunction "2_2") (pintype "passive"))
      (node (ref "U14") (pin "27") (pinfunction "SADDR_27") (pintype "passive"))
      (node (ref "U9") (pin "N17") (pinfunction "IO_L23P_T3_34_N17") (pintype "bidirectional"))
    )
    (net (code "35") (name "/S0_CLK") (class "Default")
      (node (ref "U14") (pin "28") (pinfunction "SCLK_28") (pintype "passive"))
      (node (ref "U9") (pin "P18") (pinfunction "IO_L23N_T3_34_P18") (pintype "bidirectional"))
    )
    (net (code "36") (name "/S0_DATA") (class "Default")
      (node (ref "U14") (pin "25") (pinfunction "SDATA_25") (pintype "passive"))
      (node (ref "U9") (pin "P15") (pinfunction "IO_L24P_T3_34_P15") (pintype "bidirectional"))
    )
    (net (code "37") (name "/S0_DOUT0") (class "Default")
      (node (ref "U14") (pin "43") (pinfunction "DOUT0_43") (pintype "passive"))
      (node (ref "U9") (pin "U20") (pinfunction "IO_L15N_T2_DQS_34_U20") (pintype "bidirectional"))
    )
    (net (code "38") (name "/S0_DOUT1") (class "Default")
      (node (ref "U14") (pin "44") (pinfunction "DOUT1_44") (pintype "passive"))
      (node (ref "U9") (pin "V20") (pinfunction "IO_L16P_T2_34_V20") (pintype "bidirectional"))
    )
    (net (code "39") (name "/S0_DOUT2") (class "Default")
      (node (ref "U14") (pin "45") (pinfunction "DOUT2_45") (pintype "passive"))
      (node (ref "U9") (pin "W20") (pinfunction "IO_L16N_T2_34_W20") (pintype "bidirectional"))
    )
    (net (code "40") (name "/S0_DOUT3") (class "Default")
      (node (ref "U14") (pin "46") (pinfunction "DOUT3_46") (pintype "passive"))
      (node (ref "U9") (pin "Y18") (pinfunction "IO_L17P_T2_34_Y18") (pintype "bidirectional"))
    )
    (net (code "41") (name "/S0_DOUT4") (class "Default")
      (node (ref "U14") (pin "47") (pinfunction "DOUT4_47") (pintype "passive"))
      (node (ref "U9") (pin "Y19") (pinfunction "IO_L17N_T2_34_Y19") (pintype "bidirectional"))
    )
    (net (code "42") (name "/S0_DOUT5") (class "Default")
      (node (ref "U14") (pin "48") (pinfunction "DOUT5_48") (pintype "passive"))
      (node (ref "U9") (pin "V16") (pinfunction "IO_L18P_T2_34_V16") (pintype "bidirectional"))
    )
    (net (code "43") (name "/S0_DOUT6") (class "Default")
      (node (ref "U14") (pin "1") (pinfunction "DOUT6_1") (pintype "passive"))
      (node (ref "U9") (pin "W16") (pinfunction "IO_L18N_T2_34_W16") (pintype "bidirectional"))
    )
    (net (code "44") (name "/S0_DOUT7") (class "Default")
      (node (ref "U14") (pin "2") (pinfunction "DOUT7_2") (pintype "passive"))
      (node (ref "U9") (pin "R16") (pinfunction "IO_L19P_T3_34_R16") (pintype "bidirectional"))
    )
    (net (code "45") (name "/S0_DOUT8") (class "Default")
      (node (ref "U14") (pin "3") (pinfunction "DOUT8_3") (pintype "passive"))
      (node (ref "U9") (pin "R17") (pinfunction "IO_L19N_T3_VREF_34_R17") (pintype "bidirectional"))
    )
    (net (code "46") (name "/S0_DOUT9") (class "Default")
      (node (ref "U14") (pin "4") (pinfunction "DOUT9_4") (pintype "passive"))
      (node (ref "U9") (pin "T17") (pinfunction "IO_L20P_T3_34_T17") (pintype "bidirectional"))
    )
    (net (code "47") (name "/S0_DOUT10") (class "Default")
      (node (ref "U14") (pin "5") (pinfunction "DOUT10_5") (pintype "passive"))
      (node (ref "U9") (pin "R18") (pinfunction "IO_L20N_T3_34_R18") (pintype "bidirectional"))
    )
    (net (code "48") (name "/S0_DOUT11") (class "Default")
      (node (ref "U14") (pin "6") (pinfunction "DOUT11_6") (pintype "passive"))
      (node (ref "U9") (pin "V17") (pinfunction "IO_L21P_T3_DQS_34_V17") (pintype "bidirectional"))
    )
    (net (code "49") (name "/S0_FV") (class "Default")
      (node (ref "U14") (pin "22") (pinfunction "FRAME_VALID_22") (pintype "passive"))
      (node (ref "U9") (pin "W18") (pinfunction "IO_L22P_T3_34_W18") (pintype "bidirectional"))
    )
    (net (code "50") (name "/S0_LV") (class "Default")
      (node (ref "U14") (pin "26") (pinfunction "LINE_VALID_26") (pintype "passive"))
      (node (ref "U9") (pin "V18") (pinfunction "IO_L21N_T3_DQS_34_V18") (pintype "bidirectional"))
    )
    (net (code "51") (name "/S0_PCK") (class "Default")
      (node (ref "U14") (pin "21") (pinfunction "PIXCLK_21") (pintype "passive"))
      (node (ref "U9") (pin "W19") (pinfunction "IO_L22N_T3_34_W19") (pintype "bidirectional"))
    )
    (net (code "52") (name "/S_CLK") (class "Default")
      (node (ref "R74") (pin "1") (pinfunction "1_1") (pintype "passive"))
      (node (ref "U14") (pin "9") (pinfunction "EXTCLK_9") (pintype "passive"))
      (node (ref "U9") (pin "P20") (pinfunction "IO_L14N_T2_SRCC_34_P20") (pintype "bidirectional"))
    )
    (net (code "53") (name "/S_CLK_EN") (class "Default")
      (node (ref "R73") (pin "2") (pinfunction "2_2") (pintype "passive"))
      (node (ref "U9") (pin "U14") (pinfunction "IO_L11P_T1_SRCC_34_U14") (pintype "bidirectional"))
    )
    (net (code "54") (name "/S_SHUT") (class "Default")
      (node (ref "U14") (pin "34") (pinfunction "SHUTTER_34") (pintype "passive"))
      (node (ref "U9") (pin "N20") (pinfunction "IO_L14P_T2_SRCC_34_N20") (pintype "bidirectional"))
    )
    (net (code "55") (name "/S_TRIG") (class "Default")
      (node (ref "U14") (pin "33") (pinfunction "TRIGGER_33") (pintype "passive"))
      (node (ref "U9") (pin "T19") (pinfunction "IO_25_34_T19") (pintype "bidirectional"))
    )
    (net (code "56") (name "/~{S0_EN}") (class "Default")
      (node (ref "R78") (pin "1") (pinfunction "1_1") (pintype "passive"))
      (node (ref "U14") (pin "32") (pinfunction "OE_BAR_32") (pintype "passive"))
      (node (ref "U9") (pin "T20") (pinfunction "IO_L15P_T2_DQS_34_T20") (pintype "bidirectional"))
    )
    (net (code "57") (name "/~{S0_RST_R}") (class "Default")
      (node (ref "R77") (pin "1") (pinfunction "1_1") (pintype "passive"))
      (node (ref "U14") (pin "31") (pinfunction "RESET_BAR_31") (pintype "passive"))
    )
    (net (code "58") (name "/~{S0_RST}") (class "Default")
      (node (ref "R77") (pin "2") (pinfunction "2_2") (pintype "passive"))
      (node (ref "U9") (pin "P16") (pinfunction "IO_L24N_T3_34_P16") (pintype "bidirectional"))
    )
    (net (code "59") (name "GND") (class "Default")
      (node (ref "C118") (pin "2") (pinfunction "2_2") (pintype "passive"))
      (node (ref "C119") (pin "1") (pinfunction "1_1") (pintype "passive"))
      (node (ref "C120") (pin "1") (pinfunction "1_1") (pintype "passive"))
      (node (ref "C121") (pin "1") (pinfunction "1_1") (pintype "passive"))
      (node (ref "C122") (pin "1") (pinfunction "1_1") (pintype "passive"))
      (node (ref "C123") (pin "1") (pinfunction "1_1") (pintype "passive"))
      (node (ref "C124") (pin "1") (pinfunction "1_1") (pintype "passive"))
      (node (ref "C125") (pin "1") (pinfunction "1_1") (pintype "passive"))
      (node (ref "C126") (pin "1") (pinfunction "1_1") (pintype "passive"))
      (node (ref "C127") (pin "1") (pinfunction "1_1") (pintype "passive"))
      (node (ref "C128") (pin "1") (pinfunction "1_1") (pintype "passive"))
      (node (ref "C129") (pin "1") (pinfunction "1_1") (pintype "passive"))
      (node (ref "C130") (pin "1") (pinfunction "1_1") (pintype "passive"))
      (node (ref "C131") (pin "1") (pinfunction "1_1") (pintype "passive"))
      (node (ref "C132") (pin "1") (pinfunction "1_1") (pintype "passive"))
      (node (ref "C133") (pin "1") (pinfunction "1_1") (pintype "passive"))
      (node (ref "C134") (pin "1") (pinfunction "1_1") (pintype "passive"))
      (node (ref "C135") (pin "1") (pinfunction "1_1") (pintype "passive"))
      (node (ref "C136") (pin "1") (pinfunction "1_1") (pintype "passive"))
      (node (ref "C137") (pin "1") (pinfunction "1_1") (pintype "passive"))
      (node (ref "C138") (pin "1") (pinfunction "1_1") (pintype "passive"))
      (node (ref "C139") (pin "1") (pinfunction "1_1") (pintype "passive"))
      (node (ref "C140") (pin "1") (pinfunction "1_1") (pintype "passive"))
      (node (ref "C141") (pin "1") (pinfunction "1_1") (pintype "passive"))
      (node (ref "C142") (pin "1") (pinfunction "1_1") (pintype "passive"))
      (node (ref "C143") (pin "1") (pinfunction "1_1") (pintype "passive"))
      (node (ref "C144") (pin "1") (pinfunction "1_1") (pintype "passive"))
      (node (ref "C145") (pin "1") (pinfunction "1_1") (pintype "passive"))
      (node (ref "C146") (pin "1") (pinfunction "1_1") (pintype "passive"))
      (node (ref "C147") (pin "1") (pinfunction "1_1") (pintype "passive"))
      (node (ref "C148") (pin "1") (pinfunction "1_1") (pintype "passive"))
      (node (ref "C149") (pin "1") (pinfunction "1_1") (pintype "passive"))
      (node (ref "C150") (pin "1") (pinfunction "1_1") (pintype "passive"))
      (node (ref "C151") (pin "1") (pinfunction "1_1") (pintype "passive"))
      (node (ref "C152") (pin "1") (pinfunction "1_1") (pintype "passive"))
      (node (ref "C153") (pin "1") (pinfunction "1_1") (pintype "passive"))
      (node (ref "C154") (pin "1") (pinfunction "1_1") (pintype "passive"))
      (node (ref "C155") (pin "1") (pinfunction "1_1") (pintype "passive"))
      (node (ref "C156") (pin "1") (pinfunction "1_1") (pintype "passive"))
      (node (ref "C157") (pin "1") (pinfunction "1_1") (pintype "passive"))
      (node (ref "C158") (pin "1") (pinfunction "1_1") (pintype "passive"))
      (node (ref "J3") (pin "1") (pinfunction "1_1") (pintype "passive"))
      (node (ref "J3") (pin "10") (pinfunction "10_10") (pintype "passive"))
      (node (ref "J3") (pin "13") (pinfunction "13_13") (pintype "passive"))
      (node (ref "J3") (pin "16") (pinfunction "16_16") (pintype "passive"))
      (node (ref "J3") (pin "19") (pinfunction "19_19") (pintype "passive"))
      (node (ref "J3") (pin "4") (pinfunction "4_4") (pintype "passive"))
      (node (ref "J3") (pin "7") (pinfunction "7_7") (pintype "passive"))
      (node (ref "J3") (pin "MP1") (pinfunction "MP1_MP1") (pintype "passive"))
      (node (ref "J3") (pin "MP2") (pinfunction "MP2_MP2") (pintype "passive"))
      (node (ref "OSC1") (pin "2") (pinfunction "GND_2") (pintype "power_in"))
      (node (ref "Q4") (pin "2") (pinfunction "E_2") (pintype "passive"))
      (node (ref "R75") (pin "1") (pinfunction "1_1") (pintype "passive"))
      (node (ref "U14") (pin "11") (pinfunction "AGND_11") (pintype "passive"))
      (node (ref "U14") (pin "14") (pinfunction "DGND_14") (pintype "passive"))
      (node (ref "U14") (pin "17") (pinfunction "AGND_17") (pintype "passive"))
      (node (ref "U14") (pin "23") (pinfunction "TEST_23") (pintype "passive"))
      (node (ref "U14") (pin "24") (pinfunction "DGND_24") (pintype "passive"))
      (node (ref "U14") (pin "36") (pinfunction "AGND_36") (pintype "passive"))
      (node (ref "U14") (pin "39") (pinfunction "AGND_39") (pintype "passive"))
      (node (ref "U14") (pin "40") (pinfunction "DGND_40") (pintype "passive"))
      (node (ref "U14") (pin "7") (pinfunction "DGND_7") (pintype "passive"))
    )
    (net (code "60") (name "Net-(OSC1-OE{slash}STBY{slash}FS)") (class "Default")
      (node (ref "OSC1") (pin "1") (pinfunction "OE/STBY/FS_1") (pintype "power_in"))
      (node (ref "Q4") (pin "3") (pinfunction "C_3") (pintype "passive"))
      (node (ref "R72") (pin "2") (pinfunction "2_2") (pintype "passive"))
    )
    (net (code "61") (name "Net-(OSC1-OUT)") (class "Default")
      (node (ref "OSC1") (pin "3") (pinfunction "OUT_3") (pintype "power_in"))
      (node (ref "R74") (pin "2") (pinfunction "2_2") (pintype "passive"))
    )
    (net (code "62") (name "Net-(Q4-B)") (class "Default")
      (node (ref "Q4") (pin "1") (pinfunction "B_1") (pintype "passive"))
      (node (ref "R73") (pin "1") (pinfunction "1_1") (pintype "passive"))
    )
    (net (code "63") (name "unconnected-(J3-Pad20)") (class "Default")
      (node (ref "J3") (pin "20") (pinfunction "20_20") (pintype "passive"))
    )
    (net (code "64") (name "unconnected-(U9A-IO_0_34-PadR19)") (class "Default")
      (node (ref "U9") (pin "R19") (pinfunction "IO_0_34_R19") (pintype "bidirectional+no_connect"))
    )
    (net (code "65") (name "unconnected-(U14-FLASH-Pad20)") (class "Default")
      (node (ref "U14") (pin "20") (pinfunction "FLASH_20") (pintype "passive"))
    )
    (net (code "66") (name "unconnected-(U14-NC-Pad15)") (class "Default")
      (node (ref "U14") (pin "15") (pinfunction "NC_15") (pintype "passive+no_connect"))
    )
    (net (code "67") (name "unconnected-(U14-NC-Pad35)") (class "Default")
      (node (ref "U14") (pin "35") (pinfunction "NC_35") (pintype "passive+no_connect"))
    )
  )
)
